# SSB_Transceiver_LC_Double_Tuned_Bandpass.net
KiCad netlist of a schematic drawn in EAGLE
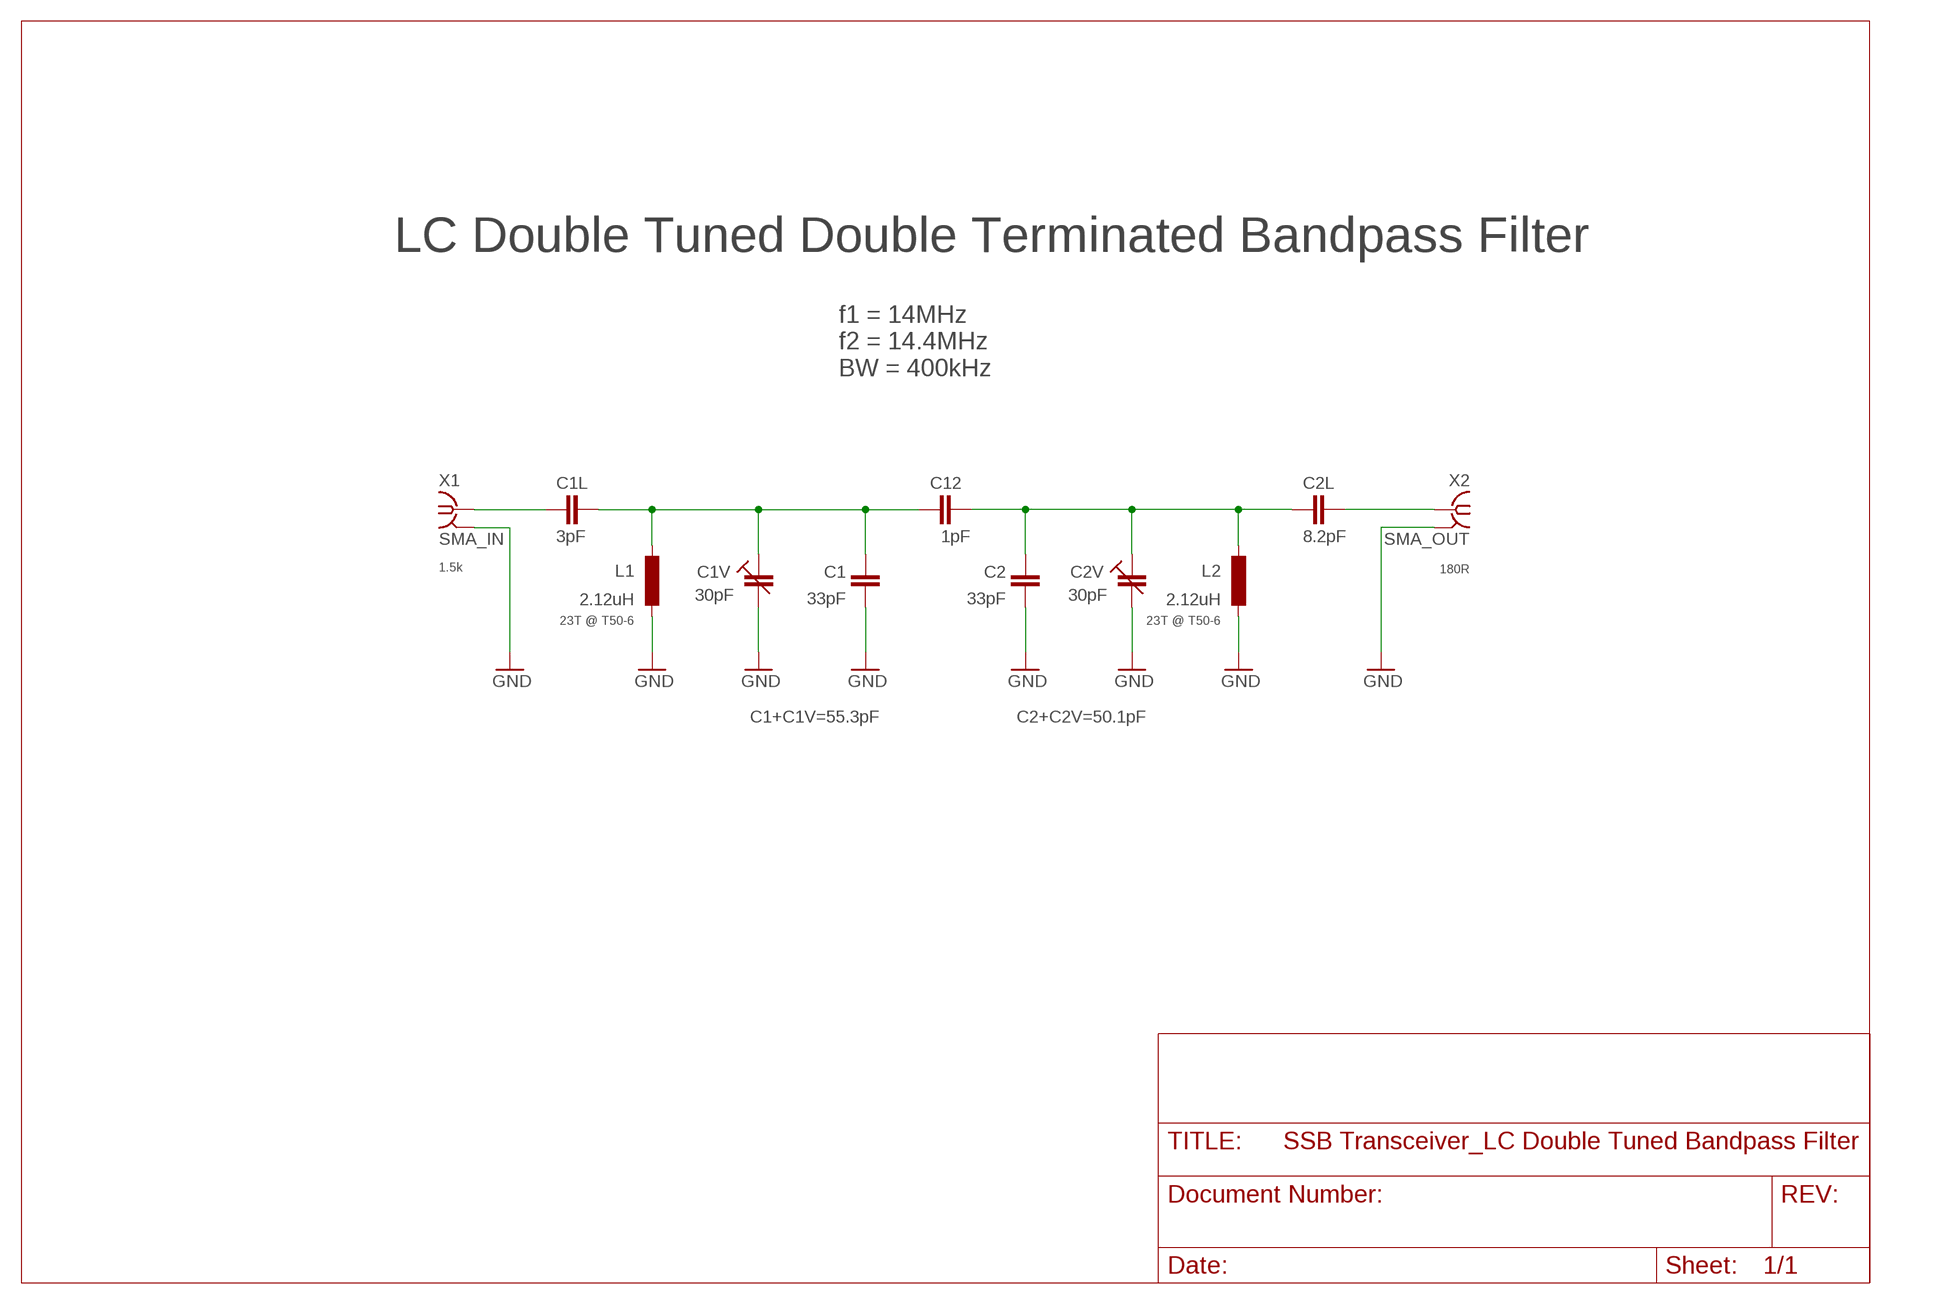
[diagram p0: schematic, sheet 1]

(export (version "E")
  (design (tool "Eeschema 10.0.6"))
  (components
    (comp (ref "C1")
      (value "33pF")
      (footprint "eagle-import:C0805")
      (libsource (lib "eagle-import") (part "C-EUC0805"))
    )
    (comp (ref "C1L")
      (value "3pF")
      (footprint "eagle-import:C0805")
      (libsource (lib "eagle-import") (part "C-EUC0805"))
    )
    (comp (ref "C1V")
      (value "30pF")
      (footprint "eagle-import:VARIABLECAP-SMD")
      (libsource (lib "eagle-import") (part "VARIABLECAP"))
    )
    (comp (ref "C2")
      (value "33pF")
      (footprint "eagle-import:C0805")
      (libsource (lib "eagle-import") (part "C-EUC0805"))
    )
    (comp (ref "C2L")
      (value "8.2pF")
      (footprint "eagle-import:C0805")
      (libsource (lib "eagle-import") (part "C-EUC0805"))
    )
    (comp (ref "C2V")
      (value "30pF")
      (footprint "eagle-import:VARIABLECAP-SMD")
      (libsource (lib "eagle-import") (part "VARIABLECAP"))
    )
    (comp (ref "C12")
      (value "1pF")
      (footprint "eagle-import:C0805")
      (libsource (lib "eagle-import") (part "C-EUC0805"))
    )
    (comp (ref "L1")
      (value "2.12uH")
      (footprint "eagle-import:T50-6SMD")
      (libsource (lib "eagle-import") (part "T50-6"))
    )
    (comp (ref "L2")
      (value "2.12uH")
      (footprint "eagle-import:T50-6SMD")
      (libsource (lib "eagle-import") (part "T50-6"))
    )
    (comp (ref "X1")
      (value "SMA_IN")
      (footprint "eagle-import:J502-ND-142-0711-821_826")
      (fields (field (name "MF") "JOHNSON COMPONENTS") (field (name "MPN") "142-0711-821"))
      (libsource (lib "eagle-import") (part "SMA-142-0711-821/826"))
    )
    (comp (ref "X2")
      (value "SMA_OUT")
      (footprint "eagle-import:J502-ND-142-0711-821_826")
      (fields (field (name "MF") "JOHNSON COMPONENTS") (field (name "MPN") "142-0711-821"))
      (libsource (lib "eagle-import") (part "SMA-142-0711-821/826"))
    )
  )
  (nets
    (net (code "1") (name "GND") (class "Default")
      (node (ref "C1") (pin "1") (pinfunction "1_1") (pintype "passive"))
      (node (ref "C1V") (pin "P$2") (pinfunction "A_P$2") (pintype "passive"))
      (node (ref "C2") (pin "1") (pinfunction "1_1") (pintype "passive"))
      (node (ref "C2V") (pin "P$2") (pinfunction "A_P$2") (pintype "passive"))
      (node (ref "L1") (pin "P$2") (pinfunction "2_P$2") (pintype "passive"))
      (node (ref "L2") (pin "P$2") (pinfunction "2_P$2") (pintype "passive"))
      (node (ref "X1") (pin "G@1") (pinfunction "2_G@1") (pintype "passive"))
      (node (ref "X1") (pin "G@2") (pinfunction "2_G@2") (pintype "passive"))
      (node (ref "X1") (pin "G@3") (pinfunction "2_G@3") (pintype "passive"))
      (node (ref "X1") (pin "G@4") (pinfunction "2_G@4") (pintype "passive"))
      (node (ref "X2") (pin "G@1") (pinfunction "2_G@1") (pintype "passive"))
      (node (ref "X2") (pin "G@2") (pinfunction "2_G@2") (pintype "passive"))
      (node (ref "X2") (pin "G@3") (pinfunction "2_G@3") (pintype "passive"))
      (node (ref "X2") (pin "G@4") (pinfunction "2_G@4") (pintype "passive"))
    )
    (net (code "2") (name "Net-(C1L-Pad1)") (class "Default")
      (node (ref "C1L") (pin "1") (pinfunction "1_1") (pintype "passive"))
      (node (ref "X1") (pin "1") (pinfunction "1_1") (pintype "passive"))
    )
    (net (code "3") (name "Net-(C1V-E)") (class "Default")
      (node (ref "C1") (pin "2") (pinfunction "2_2") (pintype "passive"))
      (node (ref "C12") (pin "1") (pinfunction "1_1") (pintype "passive"))
      (node (ref "C1L") (pin "2") (pinfunction "2_2") (pintype "passive"))
      (node (ref "C1V") (pin "P$1") (pinfunction "E_P$1") (pintype "passive"))
      (node (ref "L1") (pin "P$1") (pinfunction "1_P$1") (pintype "passive"))
    )
    (net (code "4") (name "Net-(C2L-Pad1)") (class "Default")
      (node (ref "C2L") (pin "1") (pinfunction "1_1") (pintype "passive"))
      (node (ref "X2") (pin "1") (pinfunction "1_1") (pintype "passive"))
    )
    (net (code "5") (name "Net-(C2V-E)") (class "Default")
      (node (ref "C12") (pin "2") (pinfunction "2_2") (pintype "passive"))
      (node (ref "C2") (pin "2") (pinfunction "2_2") (pintype "passive"))
      (node (ref "C2L") (pin "2") (pinfunction "2_2") (pintype "passive"))
      (node (ref "C2V") (pin "P$1") (pinfunction "E_P$1") (pintype "passive"))
      (node (ref "L2") (pin "P$1") (pinfunction "1_P$1") (pintype "passive"))
    )
  )
)
